# ZHSD-ZYNQ-PWR.net
KiCad netlist of a schematic drawn in Altium Designer
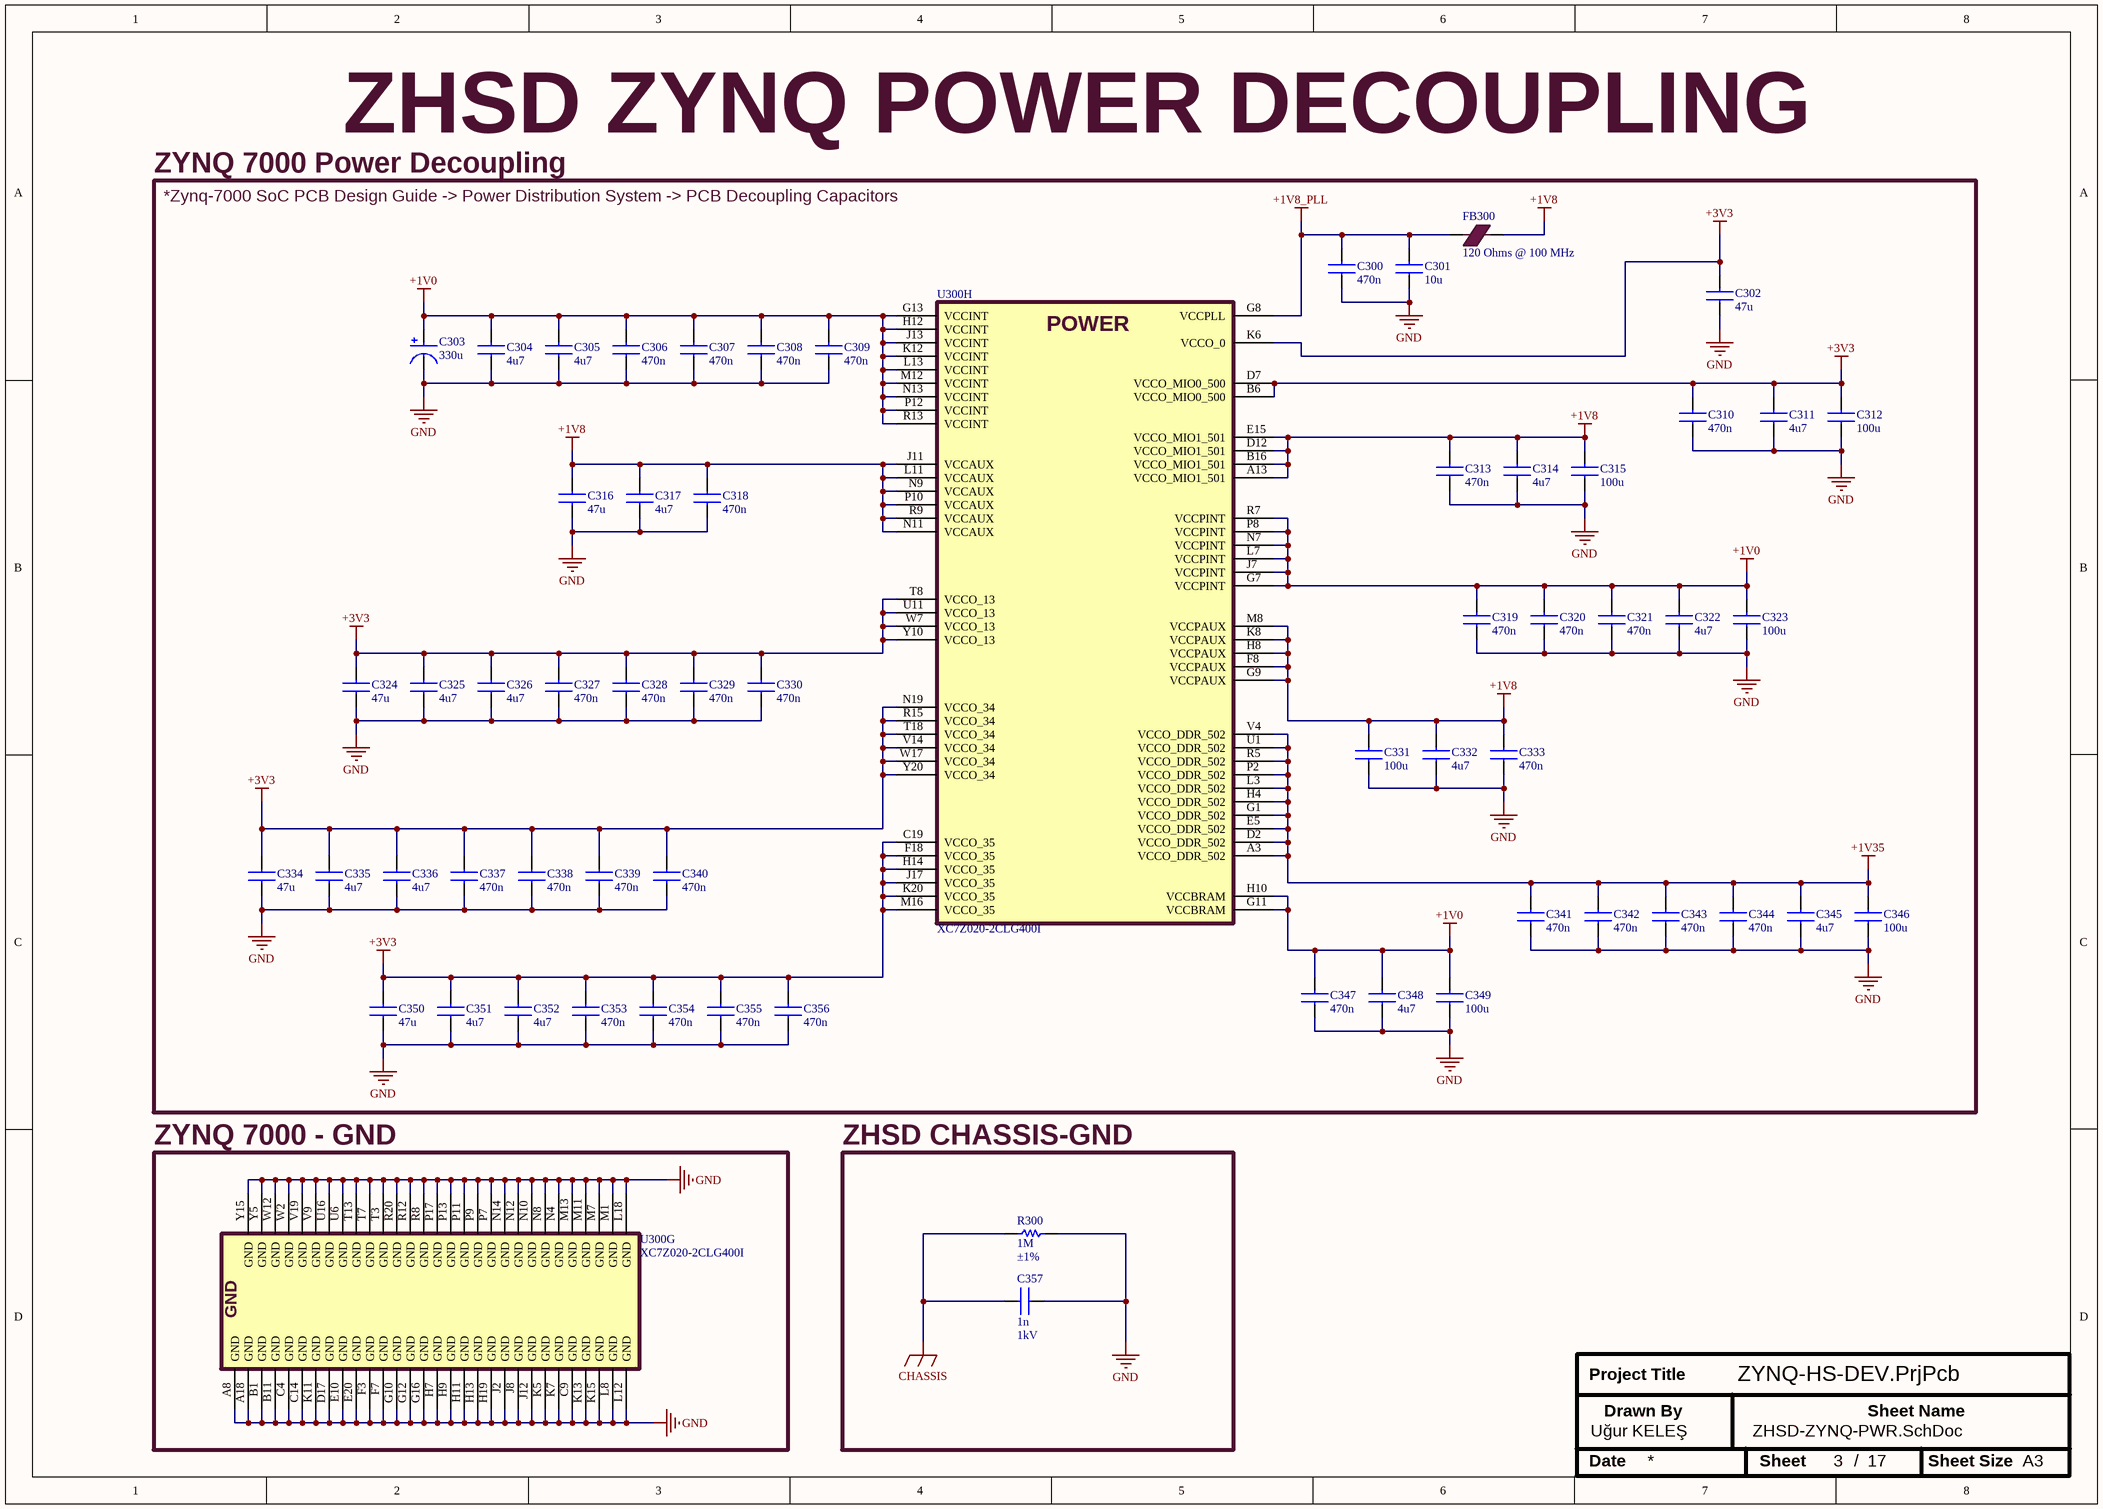
[diagram p0: ZHSD-ZYNQ-PWR.SchDoc]

(export (version "E")
  (design (tool "Eeschema 10.0.6"))
  (components
    (comp (ref "C300")
      (value "470n")
      (footprint "0402CAPC1005X06N")
      (description "CAP CER 0.47UF 6.3V X5R 0402(1005) ±10%")
      (fields (field (name "MANUFACTURER") "Murata Electronics") (field (name "MPN") "GRM155R60J474KE19D"))
      (libsource (lib "UK_Library") (part "GRM155R60J474KE19D"))
    )
    (comp (ref "C301")
      (value "10u")
      (footprint "0603CAPC1608X09N")
      (description "CAP CER 10UF 4V X5R 0603 (1608) ±20%")
      (fields (field (name "MANUFACTURER") "Murata Electronics") (field (name "MPN") "GRM188R60G106ME47D"))
      (libsource (lib "UK_Library") (part "GRM188R60G106ME47D"))
    )
    (comp (ref "C302")
      (value "47u")
      (footprint "1210CAPC3225X27N")
      (description "CAP CER 47UF 6.3V X7R 1210 1210 (3225) ±20%")
      (fields (field (name "MANUFACTURER") "Murata Electronics") (field (name "MPN") "GRM32ER70J476ME20L"))
      (libsource (lib "UK_Library") (part "GRM32ER70J476ME20L"))
    )
    (comp (ref "C303")
      (value "330u")
      (footprint "T525D337M006ATE025")
      (description "CAP TANT POLY 330UF 6.3V 2917 (7343) ±20%")
      (fields (field (name "MANUFACTURER") "KEMET") (field (name "MPN") "T525D337M006ATE025"))
      (libsource (lib "UK_Library") (part "T525D337M006ATE025"))
    )
    (comp (ref "C304")
      (value "4u7")
      (footprint "0603CAPC1608X09N")
      (description "CAP CER 4.7UF 10V X5R 0603 (1608) ±10%")
      (fields
        (field (name "MANUFACTURER") "Samsung Electro-Mechanics")
        (field (name "MPN") "CL10A475KP8NNNC")
      )
      (libsource (lib "UK_Library") (part "CL10A475KP8NNNC"))
    )
    (comp (ref "C305")
      (value "4u7")
      (footprint "0603CAPC1608X09N")
      (description "CAP CER 4.7UF 10V X5R 0603 (1608) ±10%")
      (fields
        (field (name "MANUFACTURER") "Samsung Electro-Mechanics")
        (field (name "MPN") "CL10A475KP8NNNC")
      )
      (libsource (lib "UK_Library") (part "CL10A475KP8NNNC"))
    )
    (comp (ref "C306")
      (value "470n")
      (footprint "0402CAPC1005X06N")
      (description "CAP CER 0.47UF 6.3V X5R 0402(1005) ±10%")
      (fields (field (name "MANUFACTURER") "Murata Electronics") (field (name "MPN") "GRM155R60J474KE19D"))
      (libsource (lib "UK_Library") (part "GRM155R60J474KE19D"))
    )
    (comp (ref "C307")
      (value "470n")
      (footprint "0402CAPC1005X06N")
      (description "CAP CER 0.47UF 6.3V X5R 0402(1005) ±10%")
      (fields (field (name "MANUFACTURER") "Murata Electronics") (field (name "MPN") "GRM155R60J474KE19D"))
      (libsource (lib "UK_Library") (part "GRM155R60J474KE19D"))
    )
    (comp (ref "C308")
      (value "470n")
      (footprint "0402CAPC1005X06N")
      (description "CAP CER 0.47UF 6.3V X5R 0402(1005) ±10%")
      (fields (field (name "MANUFACTURER") "Murata Electronics") (field (name "MPN") "GRM155R60J474KE19D"))
      (libsource (lib "UK_Library") (part "GRM155R60J474KE19D"))
    )
    (comp (ref "C309")
      (value "470n")
      (footprint "0402CAPC1005X06N")
      (description "CAP CER 0.47UF 6.3V X5R 0402(1005) ±10%")
      (fields (field (name "MANUFACTURER") "Murata Electronics") (field (name "MPN") "GRM155R60J474KE19D"))
      (libsource (lib "UK_Library") (part "GRM155R60J474KE19D"))
    )
    (comp (ref "C310")
      (value "470n")
      (footprint "0402CAPC1005X06N")
      (description "CAP CER 0.47UF 6.3V X5R 0402(1005) ±10%")
      (fields (field (name "MANUFACTURER") "Murata Electronics") (field (name "MPN") "GRM155R60J474KE19D"))
      (libsource (lib "UK_Library") (part "GRM155R60J474KE19D"))
    )
    (comp (ref "C311")
      (value "4u7")
      (footprint "0603CAPC1608X09N")
      (description "CAP CER 4.7UF 10V X5R 0603 (1608) ±10%")
      (fields
        (field (name "MANUFACTURER") "Samsung Electro-Mechanics")
        (field (name "MPN") "CL10A475KP8NNNC")
      )
      (libsource (lib "UK_Library") (part "CL10A475KP8NNNC"))
    )
    (comp (ref "C312")
      (value "100u")
      (footprint "1210CAPC3225X27N")
      (description "CAP CER 100UF 4V X7U 1210 (3225) ±20%")
      (fields (field (name "MANUFACTURER") "Murata Electronics") (field (name "MPN") "GRM32EE70G107ME19L"))
      (libsource (lib "UK_Library") (part "GRM32EE70G107ME19L"))
    )
    (comp (ref "C313")
      (value "470n")
      (footprint "0402CAPC1005X06N")
      (description "CAP CER 0.47UF 6.3V X5R 0402(1005) ±10%")
      (fields (field (name "MANUFACTURER") "Murata Electronics") (field (name "MPN") "GRM155R60J474KE19D"))
      (libsource (lib "UK_Library") (part "GRM155R60J474KE19D"))
    )
    (comp (ref "C314")
      (value "4u7")
      (footprint "0603CAPC1608X09N")
      (description "CAP CER 4.7UF 10V X5R 0603 (1608) ±10%")
      (fields
        (field (name "MANUFACTURER") "Samsung Electro-Mechanics")
        (field (name "MPN") "CL10A475KP8NNNC")
      )
      (libsource (lib "UK_Library") (part "CL10A475KP8NNNC"))
    )
    (comp (ref "C315")
      (value "100u")
      (footprint "1210CAPC3225X27N")
      (description "CAP CER 100UF 4V X7U 1210 (3225) ±20%")
      (fields (field (name "MANUFACTURER") "Murata Electronics") (field (name "MPN") "GRM32EE70G107ME19L"))
      (libsource (lib "UK_Library") (part "GRM32EE70G107ME19L"))
    )
    (comp (ref "C316")
      (value "47u")
      (footprint "1210CAPC3225X27N")
      (description "CAP CER 47UF 6.3V X7R 1210 1210 (3225) ±20%")
      (fields (field (name "MANUFACTURER") "Murata Electronics") (field (name "MPN") "GRM32ER70J476ME20L"))
      (libsource (lib "UK_Library") (part "GRM32ER70J476ME20L"))
    )
    (comp (ref "C317")
      (value "4u7")
      (footprint "0603CAPC1608X09N")
      (description "CAP CER 4.7UF 10V X5R 0603 (1608) ±10%")
      (fields
        (field (name "MANUFACTURER") "Samsung Electro-Mechanics")
        (field (name "MPN") "CL10A475KP8NNNC")
      )
      (libsource (lib "UK_Library") (part "CL10A475KP8NNNC"))
    )
    (comp (ref "C318")
      (value "470n")
      (footprint "0402CAPC1005X06N")
      (description "CAP CER 0.47UF 6.3V X5R 0402(1005) ±10%")
      (fields (field (name "MANUFACTURER") "Murata Electronics") (field (name "MPN") "GRM155R60J474KE19D"))
      (libsource (lib "UK_Library") (part "GRM155R60J474KE19D"))
    )
    (comp (ref "C319")
      (value "470n")
      (footprint "0402CAPC1005X06N")
      (description "CAP CER 0.47UF 6.3V X5R 0402(1005) ±10%")
      (fields (field (name "MANUFACTURER") "Murata Electronics") (field (name "MPN") "GRM155R60J474KE19D"))
      (libsource (lib "UK_Library") (part "GRM155R60J474KE19D"))
    )
    (comp (ref "C320")
      (value "470n")
      (footprint "0402CAPC1005X06N")
      (description "CAP CER 0.47UF 6.3V X5R 0402(1005) ±10%")
      (fields (field (name "MANUFACTURER") "Murata Electronics") (field (name "MPN") "GRM155R60J474KE19D"))
      (libsource (lib "UK_Library") (part "GRM155R60J474KE19D"))
    )
    (comp (ref "C321")
      (value "470n")
      (footprint "0402CAPC1005X06N")
      (description "CAP CER 0.47UF 6.3V X5R 0402(1005) ±10%")
      (fields (field (name "MANUFACTURER") "Murata Electronics") (field (name "MPN") "GRM155R60J474KE19D"))
      (libsource (lib "UK_Library") (part "GRM155R60J474KE19D"))
    )
    (comp (ref "C322")
      (value "4u7")
      (footprint "0603CAPC1608X09N")
      (description "CAP CER 4.7UF 10V X5R 0603 (1608) ±10%")
      (fields
        (field (name "MANUFACTURER") "Samsung Electro-Mechanics")
        (field (name "MPN") "CL10A475KP8NNNC")
      )
      (libsource (lib "UK_Library") (part "CL10A475KP8NNNC"))
    )
    (comp (ref "C323")
      (value "100u")
      (footprint "1210CAPC3225X27N")
      (description "CAP CER 100UF 4V X7U 1210 (3225) ±20%")
      (fields (field (name "MANUFACTURER") "Murata Electronics") (field (name "MPN") "GRM32EE70G107ME19L"))
      (libsource (lib "UK_Library") (part "GRM32EE70G107ME19L"))
    )
    (comp (ref "C324")
      (value "47u")
      (footprint "1210CAPC3225X27N")
      (description "CAP CER 47UF 6.3V X7R 1210 1210 (3225) ±20%")
      (fields (field (name "MANUFACTURER") "Murata Electronics") (field (name "MPN") "GRM32ER70J476ME20L"))
      (libsource (lib "UK_Library") (part "GRM32ER70J476ME20L"))
    )
    (comp (ref "C325")
      (value "4u7")
      (footprint "0603CAPC1608X09N")
      (description "CAP CER 4.7UF 10V X5R 0603 (1608) ±10%")
      (fields
        (field (name "MANUFACTURER") "Samsung Electro-Mechanics")
        (field (name "MPN") "CL10A475KP8NNNC")
      )
      (libsource (lib "UK_Library") (part "CL10A475KP8NNNC"))
    )
    (comp (ref "C326")
      (value "4u7")
      (footprint "0603CAPC1608X09N")
      (description "CAP CER 4.7UF 10V X5R 0603 (1608) ±10%")
      (fields
        (field (name "MANUFACTURER") "Samsung Electro-Mechanics")
        (field (name "MPN") "CL10A475KP8NNNC")
      )
      (libsource (lib "UK_Library") (part "CL10A475KP8NNNC"))
    )
    (comp (ref "C327")
      (value "470n")
      (footprint "0402CAPC1005X06N")
      (description "CAP CER 0.47UF 6.3V X5R 0402(1005) ±10%")
      (fields (field (name "MANUFACTURER") "Murata Electronics") (field (name "MPN") "GRM155R60J474KE19D"))
      (libsource (lib "UK_Library") (part "GRM155R60J474KE19D"))
    )
    (comp (ref "C328")
      (value "470n")
      (footprint "0402CAPC1005X06N")
      (description "CAP CER 0.47UF 6.3V X5R 0402(1005) ±10%")
      (fields (field (name "MANUFACTURER") "Murata Electronics") (field (name "MPN") "GRM155R60J474KE19D"))
      (libsource (lib "UK_Library") (part "GRM155R60J474KE19D"))
    )
    (comp (ref "C329")
      (value "470n")
      (footprint "0402CAPC1005X06N")
      (description "CAP CER 0.47UF 6.3V X5R 0402(1005) ±10%")
      (fields (field (name "MANUFACTURER") "Murata Electronics") (field (name "MPN") "GRM155R60J474KE19D"))
      (libsource (lib "UK_Library") (part "GRM155R60J474KE19D"))
    )
    (comp (ref "C330")
      (value "470n")
      (footprint "0402CAPC1005X06N")
      (description "CAP CER 0.47UF 6.3V X5R 0402(1005) ±10%")
      (fields (field (name "MANUFACTURER") "Murata Electronics") (field (name "MPN") "GRM155R60J474KE19D"))
      (libsource (lib "UK_Library") (part "GRM155R60J474KE19D"))
    )
    (comp (ref "C331")
      (value "100u")
      (footprint "1210CAPC3225X27N")
      (description "CAP CER 100UF 4V X7U 1210 (3225) ±20%")
      (fields (field (name "MANUFACTURER") "Murata Electronics") (field (name "MPN") "GRM32EE70G107ME19L"))
      (libsource (lib "UK_Library") (part "GRM32EE70G107ME19L"))
    )
    (comp (ref "C332")
      (value "4u7")
      (footprint "0603CAPC1608X09N")
      (description "CAP CER 4.7UF 10V X5R 0603 (1608) ±10%")
      (fields
        (field (name "MANUFACTURER") "Samsung Electro-Mechanics")
        (field (name "MPN") "CL10A475KP8NNNC")
      )
      (libsource (lib "UK_Library") (part "CL10A475KP8NNNC"))
    )
    (comp (ref "C333")
      (value "470n")
      (footprint "0402CAPC1005X06N")
      (description "CAP CER 0.47UF 6.3V X5R 0402(1005) ±10%")
      (fields (field (name "MANUFACTURER") "Murata Electronics") (field (name "MPN") "GRM155R60J474KE19D"))
      (libsource (lib "UK_Library") (part "GRM155R60J474KE19D"))
    )
    (comp (ref "C334")
      (value "47u")
      (footprint "1210CAPC3225X27N")
      (description "CAP CER 47UF 6.3V X7R 1210 1210 (3225) ±20%")
      (fields (field (name "MANUFACTURER") "Murata Electronics") (field (name "MPN") "GRM32ER70J476ME20L"))
      (libsource (lib "UK_Library") (part "GRM32ER70J476ME20L"))
    )
    (comp (ref "C335")
      (value "4u7")
      (footprint "0603CAPC1608X09N")
      (description "CAP CER 4.7UF 10V X5R 0603 (1608) ±10%")
      (fields
        (field (name "MANUFACTURER") "Samsung Electro-Mechanics")
        (field (name "MPN") "CL10A475KP8NNNC")
      )
      (libsource (lib "UK_Library") (part "CL10A475KP8NNNC"))
    )
    (comp (ref "C336")
      (value "4u7")
      (footprint "0603CAPC1608X09N")
      (description "CAP CER 4.7UF 10V X5R 0603 (1608) ±10%")
      (fields
        (field (name "MANUFACTURER") "Samsung Electro-Mechanics")
        (field (name "MPN") "CL10A475KP8NNNC")
      )
      (libsource (lib "UK_Library") (part "CL10A475KP8NNNC"))
    )
    (comp (ref "C337")
      (value "470n")
      (footprint "0402CAPC1005X06N")
      (description "CAP CER 0.47UF 6.3V X5R 0402(1005) ±10%")
      (fields (field (name "MANUFACTURER") "Murata Electronics") (field (name "MPN") "GRM155R60J474KE19D"))
      (libsource (lib "UK_Library") (part "GRM155R60J474KE19D"))
    )
    (comp (ref "C338")
      (value "470n")
      (footprint "0402CAPC1005X06N")
      (description "CAP CER 0.47UF 6.3V X5R 0402(1005) ±10%")
      (fields (field (name "MANUFACTURER") "Murata Electronics") (field (name "MPN") "GRM155R60J474KE19D"))
      (libsource (lib "UK_Library") (part "GRM155R60J474KE19D"))
    )
    (comp (ref "C339")
      (value "470n")
      (footprint "0402CAPC1005X06N")
      (description "CAP CER 0.47UF 6.3V X5R 0402(1005) ±10%")
      (fields (field (name "MANUFACTURER") "Murata Electronics") (field (name "MPN") "GRM155R60J474KE19D"))
      (libsource (lib "UK_Library") (part "GRM155R60J474KE19D"))
    )
    (comp (ref "C340")
      (value "470n")
      (footprint "0402CAPC1005X06N")
      (description "CAP CER 0.47UF 6.3V X5R 0402(1005) ±10%")
      (fields (field (name "MANUFACTURER") "Murata Electronics") (field (name "MPN") "GRM155R60J474KE19D"))
      (libsource (lib "UK_Library") (part "GRM155R60J474KE19D"))
    )
    (comp (ref "C341")
      (value "470n")
      (footprint "0402CAPC1005X06N")
      (description "CAP CER 0.47UF 6.3V X5R 0402(1005) ±10%")
      (fields (field (name "MANUFACTURER") "Murata Electronics") (field (name "MPN") "GRM155R60J474KE19D"))
      (libsource (lib "UK_Library") (part "GRM155R60J474KE19D"))
    )
    (comp (ref "C342")
      (value "470n")
      (footprint "0402CAPC1005X06N")
      (description "CAP CER 0.47UF 6.3V X5R 0402(1005) ±10%")
      (fields (field (name "MANUFACTURER") "Murata Electronics") (field (name "MPN") "GRM155R60J474KE19D"))
      (libsource (lib "UK_Library") (part "GRM155R60J474KE19D"))
    )
    (comp (ref "C343")
      (value "470n")
      (footprint "0402CAPC1005X06N")
      (description "CAP CER 0.47UF 6.3V X5R 0402(1005) ±10%")
      (fields (field (name "MANUFACTURER") "Murata Electronics") (field (name "MPN") "GRM155R60J474KE19D"))
      (libsource (lib "UK_Library") (part "GRM155R60J474KE19D"))
    )
    (comp (ref "C344")
      (value "470n")
      (footprint "0402CAPC1005X06N")
      (description "CAP CER 0.47UF 6.3V X5R 0402(1005) ±10%")
      (fields (field (name "MANUFACTURER") "Murata Electronics") (field (name "MPN") "GRM155R60J474KE19D"))
      (libsource (lib "UK_Library") (part "GRM155R60J474KE19D"))
    )
    (comp (ref "C345")
      (value "4u7")
      (footprint "0603CAPC1608X09N")
      (description "CAP CER 4.7UF 10V X5R 0603 (1608) ±10%")
      (fields
        (field (name "MANUFACTURER") "Samsung Electro-Mechanics")
        (field (name "MPN") "CL10A475KP8NNNC")
      )
      (libsource (lib "UK_Library") (part "CL10A475KP8NNNC"))
    )
    (comp (ref "C346")
      (value "100u")
      (footprint "1210CAPC3225X27N")
      (description "CAP CER 100UF 4V X7U 1210 (3225) ±20%")
      (fields (field (name "MANUFACTURER") "Murata Electronics") (field (name "MPN") "GRM32EE70G107ME19L"))
      (libsource (lib "UK_Library") (part "GRM32EE70G107ME19L"))
    )
    (comp (ref "C347")
      (value "470n")
      (footprint "0402CAPC1005X06N")
      (description "CAP CER 0.47UF 6.3V X5R 0402(1005) ±10%")
      (fields (field (name "MANUFACTURER") "Murata Electronics") (field (name "MPN") "GRM155R60J474KE19D"))
      (libsource (lib "UK_Library") (part "GRM155R60J474KE19D"))
    )
    (comp (ref "C348")
      (value "4u7")
      (footprint "0603CAPC1608X09N")
      (description "CAP CER 4.7UF 10V X5R 0603 (1608) ±10%")
      (fields
        (field (name "MANUFACTURER") "Samsung Electro-Mechanics")
        (field (name "MPN") "CL10A475KP8NNNC")
      )
      (libsource (lib "UK_Library") (part "CL10A475KP8NNNC"))
    )
    (comp (ref "C349")
      (value "100u")
      (footprint "1210CAPC3225X27N")
      (description "CAP CER 100UF 4V X7U 1210 (3225) ±20%")
      (fields (field (name "MANUFACTURER") "Murata Electronics") (field (name "MPN") "GRM32EE70G107ME19L"))
      (libsource (lib "UK_Library") (part "GRM32EE70G107ME19L"))
    )
    (comp (ref "C350")
      (value "47u")
      (footprint "1210CAPC3225X27N")
      (description "CAP CER 47UF 6.3V X7R 1210 1210 (3225) ±20%")
      (fields (field (name "MANUFACTURER") "Murata Electronics") (field (name "MPN") "GRM32ER70J476ME20L"))
      (libsource (lib "UK_Library") (part "GRM32ER70J476ME20L"))
    )
    (comp (ref "C351")
      (value "4u7")
      (footprint "0603CAPC1608X09N")
      (description "CAP CER 4.7UF 10V X5R 0603 (1608) ±10%")
      (fields
        (field (name "MANUFACTURER") "Samsung Electro-Mechanics")
        (field (name "MPN") "CL10A475KP8NNNC")
      )
      (libsource (lib "UK_Library") (part "CL10A475KP8NNNC"))
    )
    (comp (ref "C352")
      (value "4u7")
      (footprint "0603CAPC1608X09N")
      (description "CAP CER 4.7UF 10V X5R 0603 (1608) ±10%")
      (fields
        (field (name "MANUFACTURER") "Samsung Electro-Mechanics")
        (field (name "MPN") "CL10A475KP8NNNC")
      )
      (libsource (lib "UK_Library") (part "CL10A475KP8NNNC"))
    )
    (comp (ref "C353")
      (value "470n")
      (footprint "0402CAPC1005X06N")
      (description "CAP CER 0.47UF 6.3V X5R 0402(1005) ±10%")
      (fields (field (name "MANUFACTURER") "Murata Electronics") (field (name "MPN") "GRM155R60J474KE19D"))
      (libsource (lib "UK_Library") (part "GRM155R60J474KE19D"))
    )
    (comp (ref "C354")
      (value "470n")
      (footprint "0402CAPC1005X06N")
      (description "CAP CER 0.47UF 6.3V X5R 0402(1005) ±10%")
      (fields (field (name "MANUFACTURER") "Murata Electronics") (field (name "MPN") "GRM155R60J474KE19D"))
      (libsource (lib "UK_Library") (part "GRM155R60J474KE19D"))
    )
    (comp (ref "C355")
      (value "470n")
      (footprint "0402CAPC1005X06N")
      (description "CAP CER 0.47UF 6.3V X5R 0402(1005) ±10%")
      (fields (field (name "MANUFACTURER") "Murata Electronics") (field (name "MPN") "GRM155R60J474KE19D"))
      (libsource (lib "UK_Library") (part "GRM155R60J474KE19D"))
    )
    (comp (ref "C356")
      (value "470n")
      (footprint "0402CAPC1005X06N")
      (description "CAP CER 0.47UF 6.3V X5R 0402(1005) ±10%")
      (fields (field (name "MANUFACTURER") "Murata Electronics") (field (name "MPN") "GRM155R60J474KE19D"))
      (libsource (lib "UK_Library") (part "GRM155R60J474KE19D"))
    )
    (comp (ref "C357")
      (value "1n")
      (footprint "0805CAPC2012X14N")
      (description "CAP CER 1000PF 1KV X7R 0805 (2012) ±10%")
      (fields
        (field (name "MANUFACTURER") "YAGEO")
        (field (name "MPN") "CC0805KRX7RCBB102")
        (field (name "VOLTAGE") "1kV")
      )
      (libsource (lib "UK_Library") (part "CC0805KRX7RCBB102"))
    )
    (comp (ref "FB300")
      (value "120 Ohms @ 100 MHz")
      (footprint "0603INDC1608X08N")
      (description "FERRITE BEAD 120 OHM 0603 (1608) 3A 25mOhm")
      (fields (field (name "MANUFACTURER") "Murata Electronics") (field (name "MPN") "BLM18SG121TN1D"))
      (libsource (lib "UK_Library") (part "BLM18SG121TN1D"))
    )
    (comp (ref "R300")
      (value "1M")
      (footprint "0603RESC1608X05N")
      (description "RES SMD 1M OHM 1% 1/8W 0603 (1608)")
      (fields
        (field (name "MANUFACTURER") "Vishay Dale")
        (field (name "MPN") "CRCW06031M00FKEA")
        (field (name "TOLERANCE") "±1%")
      )
      (libsource (lib "UK_Library") (part "CRCW06031M00FKEA"))
    )
    (comp (ref "U300")
      (value "XC7Z020-2CLG400I")
      (footprint "BGA400C80P20X20_1700X1700X147")
      (fields (field (name "MANUFACTURER") "AMD/XILINX"))
      (libsource (lib "UK_Library") (part "XC7Z020-2CLG400I"))
    )
  )
  (nets
    (net (code "1") (name "+1V0") (class "Default")
      (node (ref "C303") (pin "1") (pinfunction "1_1") (pintype "passive"))
      (node (ref "C304") (pin "2") (pinfunction "2_2") (pintype "passive"))
      (node (ref "C305") (pin "2") (pinfunction "2_2") (pintype "passive"))
      (node (ref "C306") (pin "2") (pinfunction "2_2") (pintype "passive"))
      (node (ref "C307") (pin "2") (pinfunction "2_2") (pintype "passive"))
      (node (ref "C308") (pin "2") (pinfunction "2_2") (pintype "passive"))
      (node (ref "C309") (pin "2") (pinfunction "2_2") (pintype "passive"))
      (node (ref "C319") (pin "2") (pinfunction "2_2") (pintype "passive"))
      (node (ref "C320") (pin "2") (pinfunction "2_2") (pintype "passive"))
      (node (ref "C321") (pin "2") (pinfunction "2_2") (pintype "passive"))
      (node (ref "C322") (pin "2") (pinfunction "2_2") (pintype "passive"))
      (node (ref "C323") (pin "1") (pinfunction "1_1") (pintype "passive"))
      (node (ref "C347") (pin "2") (pinfunction "2_2") (pintype "passive"))
      (node (ref "C348") (pin "2") (pinfunction "2_2") (pintype "passive"))
      (node (ref "C349") (pin "1") (pinfunction "1_1") (pintype "passive"))
      (node (ref "U300") (pin "G11") (pinfunction "VCCBRAM_G11") (pintype "power_in"))
      (node (ref "U300") (pin "G13") (pinfunction "VCCINT_G13") (pintype "power_in"))
      (node (ref "U300") (pin "G7") (pinfunction "VCCPINT_G7") (pintype "power_in"))
      (node (ref "U300") (pin "H10") (pinfunction "VCCBRAM_H10") (pintype "power_in"))
      (node (ref "U300") (pin "H12") (pinfunction "VCCINT_H12") (pintype "power_in"))
      (node (ref "U300") (pin "J13") (pinfunction "VCCINT_J13") (pintype "power_in"))
      (node (ref "U300") (pin "J7") (pinfunction "VCCPINT_J7") (pintype "power_in"))
      (node (ref "U300") (pin "K12") (pinfunction "VCCINT_K12") (pintype "power_in"))
      (node (ref "U300") (pin "L13") (pinfunction "VCCINT_L13") (pintype "power_in"))
      (node (ref "U300") (pin "L7") (pinfunction "VCCPINT_L7") (pintype "power_in"))
      (node (ref "U300") (pin "M12") (pinfunction "VCCINT_M12") (pintype "power_in"))
      (node (ref "U300") (pin "N13") (pinfunction "VCCINT_N13") (pintype "power_in"))
      (node (ref "U300") (pin "N7") (pinfunction "VCCPINT_N7") (pintype "power_in"))
      (node (ref "U300") (pin "P12") (pinfunction "VCCINT_P12") (pintype "power_in"))
      (node (ref "U300") (pin "P8") (pinfunction "VCCPINT_P8") (pintype "power_in"))
      (node (ref "U300") (pin "R13") (pinfunction "VCCINT_R13") (pintype "power_in"))
      (node (ref "U300") (pin "R7") (pinfunction "VCCPINT_R7") (pintype "power_in"))
    )
    (net (code "2") (name "+1V8") (class "Default")
      (node (ref "C313") (pin "2") (pinfunction "2_2") (pintype "passive"))
      (node (ref "C314") (pin "2") (pinfunction "2_2") (pintype "passive"))
      (node (ref "C315") (pin "1") (pinfunction "1_1") (pintype "passive"))
      (node (ref "C316") (pin "2") (pinfunction "2_2") (pintype "passive"))
      (node (ref "C317") (pin "2") (pinfunction "2_2") (pintype "passive"))
      (node (ref "C318") (pin "2") (pinfunction "2_2") (pintype "passive"))
      (node (ref "C331") (pin "1") (pinfunction "1_1") (pintype "passive"))
      (node (ref "C332") (pin "2") (pinfunction "2_2") (pintype "passive"))
      (node (ref "C333") (pin "2") (pinfunction "2_2") (pintype "passive"))
      (node (ref "FB300") (pin "2") (pinfunction "2_2") (pintype "passive"))
      (node (ref "U300") (pin "A13") (pinfunction "VCCO_MIO1_501_A13") (pintype "power_in"))
      (node (ref "U300") (pin "B16") (pinfunction "VCCO_MIO1_501_B16") (pintype "power_in"))
      (node (ref "U300") (pin "D12") (pinfunction "VCCO_MIO1_501_D12") (pintype "power_in"))
      (node (ref "U300") (pin "E15") (pinfunction "VCCO_MIO1_501_E15") (pintype "power_in"))
      (node (ref "U300") (pin "F8") (pinfunction "VCCPAUX_F8") (pintype "power_in"))
      (node (ref "U300") (pin "G9") (pinfunction "VCCPAUX_G9") (pintype "power_in"))
      (node (ref "U300") (pin "H8") (pinfunction "VCCPAUX_H8") (pintype "power_in"))
      (node (ref "U300") (pin "J11") (pinfunction "VCCAUX_J11") (pintype "power_in"))
      (node (ref "U300") (pin "K8") (pinfunction "VCCPAUX_K8") (pintype "power_in"))
      (node (ref "U300") (pin "L11") (pinfunction "VCCAUX_L11") (pintype "power_in"))
      (node (ref "U300") (pin "M8") (pinfunction "VCCPAUX_M8") (pintype "power_in"))
      (node (ref "U300") (pin "N11") (pinfunction "VCCAUX_N11") (pintype "power_in"))
      (node (ref "U300") (pin "N9") (pinfunction "VCCAUX_N9") (pintype "power_in"))
      (node (ref "U300") (pin "P10") (pinfunction "VCCAUX_P10") (pintype "power_in"))
      (node (ref "U300") (pin "R9") (pinfunction "VCCAUX_R9") (pintype "power_in"))
    )
    (net (code "3") (name "+1V8_PLL") (class "Default")
      (node (ref "C300") (pin "2") (pinfunction "2_2") (pintype "passive"))
      (node (ref "C301") (pin "2") (pinfunction "2_2") (pintype "passive"))
      (node (ref "FB300") (pin "1") (pinfunction "1_1") (pintype "passive"))
      (node (ref "U300") (pin "G8") (pinfunction "VCCPLL_G8") (pintype "power_in"))
    )
    (net (code "4") (name "+1V35") (class "Default")
      (node (ref "C341") (pin "2") (pinfunction "2_2") (pintype "passive"))
      (node (ref "C342") (pin "2") (pinfunction "2_2") (pintype "passive"))
      (node (ref "C343") (pin "2") (pinfunction "2_2") (pintype "passive"))
      (node (ref "C344") (pin "2") (pinfunction "2_2") (pintype "passive"))
      (node (ref "C345") (pin "2") (pinfunction "2_2") (pintype "passive"))
      (node (ref "C346") (pin "1") (pinfunction "1_1") (pintype "passive"))
      (node (ref "U300") (pin "A3") (pinfunction "VCCO_DDR_502_A3") (pintype "power_in"))
      (node (ref "U300") (pin "D2") (pinfunction "VCCO_DDR_502_D2") (pintype "power_in"))
      (node (ref "U300") (pin "E5") (pinfunction "VCCO_DDR_502_E5") (pintype "power_in"))
      (node (ref "U300") (pin "G1") (pinfunction "VCCO_DDR_502_G1") (pintype "power_in"))
      (node (ref "U300") (pin "H4") (pinfunction "VCCO_DDR_502_H4") (pintype "power_in"))
      (node (ref "U300") (pin "L3") (pinfunction "VCCO_DDR_502_L3") (pintype "power_in"))
      (node (ref "U300") (pin "P2") (pinfunction "VCCO_DDR_502_P2") (pintype "power_in"))
      (node (ref "U300") (pin "R5") (pinfunction "VCCO_DDR_502_R5") (pintype "power_in"))
      (node (ref "U300") (pin "U1") (pinfunction "VCCO_DDR_502_U1") (pintype "power_in"))
      (node (ref "U300") (pin "V4") (pinfunction "VCCO_DDR_502_V4") (pintype "power_in"))
    )
    (net (code "5") (name "+3V3") (class "Default")
      (node (ref "C302") (pin "2") (pinfunction "2_2") (pintype "passive"))
      (node (ref "C310") (pin "2") (pinfunction "2_2") (pintype "passive"))
      (node (ref "C311") (pin "2") (pinfunction "2_2") (pintype "passive"))
      (node (ref "C312") (pin "1") (pinfunction "1_1") (pintype "passive"))
      (node (ref "C324") (pin "2") (pinfunction "2_2") (pintype "passive"))
      (node (ref "C325") (pin "2") (pinfunction "2_2") (pintype "passive"))
      (node (ref "C326") (pin "2") (pinfunction "2_2") (pintype "passive"))
      (node (ref "C327") (pin "2") (pinfunction "2_2") (pintype "passive"))
      (node (ref "C328") (pin "2") (pinfunction "2_2") (pintype "passive"))
      (node (ref "C329") (pin "2") (pinfunction "2_2") (pintype "passive"))
      (node (ref "C330") (pin "2") (pinfunction "2_2") (pintype "passive"))
      (node (ref "C334") (pin "2") (pinfunction "2_2") (pintype "passive"))
      (node (ref "C335") (pin "2") (pinfunction "2_2") (pintype "passive"))
      (node (ref "C336") (pin "2") (pinfunction "2_2") (pintype "passive"))
      (node (ref "C337") (pin "2") (pinfunction "2_2") (pintype "passive"))
      (node (ref "C338") (pin "2") (pinfunction "2_2") (pintype "passive"))
      (node (ref "C339") (pin "2") (pinfunction "2_2") (pintype "passive"))
      (node (ref "C340") (pin "2") (pinfunction "2_2") (pintype "passive"))
      (node (ref "C350") (pin "2") (pinfunction "2_2") (pintype "passive"))
      (node (ref "C351") (pin "2") (pinfunction "2_2") (pintype "passive"))
      (node (ref "C352") (pin "2") (pinfunction "2_2") (pintype "passive"))
      (node (ref "C353") (pin "2") (pinfunction "2_2") (pintype "passive"))
      (node (ref "C354") (pin "2") (pinfunction "2_2") (pintype "passive"))
      (node (ref "C355") (pin "2") (pinfunction "2_2") (pintype "passive"))
      (node (ref "C356") (pin "2") (pinfunction "2_2") (pintype "passive"))
      (node (ref "U300") (pin "B6") (pinfunction "VCCO_MIO0_500_B6") (pintype "power_in"))
      (node (ref "U300") (pin "C19") (pinfunction "VCCO_35_C19") (pintype "power_in"))
      (node (ref "U300") (pin "D7") (pinfunction "VCCO_MIO0_500_D7") (pintype "power_in"))
      (node (ref "U300") (pin "F18") (pinfunction "VCCO_35_F18") (pintype "power_in"))
      (node (ref "U300") (pin "H14") (pinfunction "VCCO_35_H14") (pintype "power_in"))
      (node (ref "U300") (pin "J17") (pinfunction "VCCO_35_J17") (pintype "power_in"))
      (node (ref "U300") (pin "K20") (pinfunction "VCCO_35_K20") (pintype "power_in"))
      (node (ref "U300") (pin "K6") (pinfunction "VCCO_0_K6") (pintype "power_in"))
      (node (ref "U300") (pin "M16") (pinfunction "VCCO_35_M16") (pintype "power_in"))
      (node (ref "U300") (pin "N19") (pinfunction "VCCO_34_N19") (pintype "power_in"))
      (node (ref "U300") (pin "R15") (pinfunction "VCCO_34_R15") (pintype "power_in"))
      (node (ref "U300") (pin "T18") (pinfunction "VCCO_34_T18") (pintype "power_in"))
      (node (ref "U300") (pin "T8") (pinfunction "VCCO_13_T8") (pintype "power_in"))
      (node (ref "U300") (pin "U11") (pinfunction "VCCO_13_U11") (pintype "power_in"))
      (node (ref "U300") (pin "V14") (pinfunction "VCCO_34_V14") (pintype "power_in"))
      (node (ref "U300") (pin "W17") (pinfunction "VCCO_34_W17") (pintype "power_in"))
      (node (ref "U300") (pin "W7") (pinfunction "VCCO_13_W7") (pintype "power_in"))
      (node (ref "U300") (pin "Y10") (pinfunction "VCCO_13_Y10") (pintype "power_in"))
      (node (ref "U300") (pin "Y20") (pinfunction "VCCO_34_Y20") (pintype "power_in"))
    )
    (net (code "6") (name "CHASSIS") (class "Default")
      (node (ref "C357") (pin "2") (pinfunction "2_2") (pintype "passive"))
      (node (ref "R300") (pin "1") (pinfunction "1_1") (pintype "passive"))
    )
    (net (code "7") (name "GND") (class "Default")
      (node (ref "C300") (pin "1") (pinfunction "1_1") (pintype "passive"))
      (node (ref "C301") (pin "1") (pinfunction "1_1") (pintype "passive"))
      (node (ref "C302") (pin "1") (pinfunction "1_1") (pintype "passive"))
      (node (ref "C303") (pin "2") (pinfunction "2_2") (pintype "passive"))
      (node (ref "C304") (pin "1") (pinfunction "1_1") (pintype "passive"))
      (node (ref "C305") (pin "1") (pinfunction "1_1") (pintype "passive"))
      (node (ref "C306") (pin "1") (pinfunction "1_1") (pintype "passive"))
      (node (ref "C307") (pin "1") (pinfunction "1_1") (pintype "passive"))
      (node (ref "C308") (pin "1") (pinfunction "1_1") (pintype "passive"))
      (node (ref "C309") (pin "1") (pinfunction "1_1") (pintype "passive"))
      (node (ref "C310") (pin "1") (pinfunction "1_1") (pintype "passive"))
      (node (ref "C311") (pin "1") (pinfunction "1_1") (pintype "passive"))
      (node (ref "C312") (pin "2") (pinfunction "2_2") (pintype "passive"))
      (node (ref "C313") (pin "1") (pinfunction "1_1") (pintype "passive"))
      (node (ref "C314") (pin "1") (pinfunction "1_1") (pintype "passive"))
      (node (ref "C315") (pin "2") (pinfunction "2_2") (pintype "passive"))
      (node (ref "C316") (pin "1") (pinfunction "1_1") (pintype "passive"))
      (node (ref "C317") (pin "1") (pinfunction "1_1") (pintype "passive"))
      (node (ref "C318") (pin "1") (pinfunction "1_1") (pintype "passive"))
      (node (ref "C319") (pin "1") (pinfunction "1_1") (pintype "passive"))
      (node (ref "C320") (pin "1") (pinfunction "1_1") (pintype "passive"))
      (node (ref "C321") (pin "1") (pinfunction "1_1") (pintype "passive"))
      (node (ref "C322") (pin "1") (pinfunction "1_1") (pintype "passive"))
      (node (ref "C323") (pin "2") (pinfunction "2_2") (pintype "passive"))
      (node (ref "C324") (pin "1") (pinfunction "1_1") (pintype "passive"))
      (node (ref "C325") (pin "1") (pinfunction "1_1") (pintype "passive"))
      (node (ref "C326") (pin "1") (pinfunction "1_1") (pintype "passive"))
      (node (ref "C327") (pin "1") (pinfunction "1_1") (pintype "passive"))
      (node (ref "C328") (pin "1") (pinfunction "1_1") (pintype "passive"))
      (node (ref "C329") (pin "1") (pinfunction "1_1") (pintype "passive"))
      (node (ref "C330") (pin "1") (pinfunction "1_1") (pintype "passive"))
      (node (ref "C331") (pin "2") (pinfunction "2_2") (pintype "passive"))
      (node (ref "C332") (pin "1") (pinfunction "1_1") (pintype "passive"))
      (node (ref "C333") (pin "1") (pinfunction "1_1") (pintype "passive"))
      (node (ref "C334") (pin "1") (pinfunction "1_1") (pintype "passive"))
      (node (ref "C335") (pin "1") (pinfunction "1_1") (pintype "passive"))
      (node (ref "C336") (pin "1") (pinfunction "1_1") (pintype "passive"))
      (node (ref "C337") (pin "1") (pinfunction "1_1") (pintype "passive"))
      (node (ref "C338") (pin "1") (pinfunction "1_1") (pintype "passive"))
      (node (ref "C339") (pin "1") (pinfunction "1_1") (pintype "passive"))
      (node (ref "C340") (pin "1") (pinfunction "1_1") (pintype "passive"))
      (node (ref "C341") (pin "1") (pinfunction "1_1") (pintype "passive"))
      (node (ref "C342") (pin "1") (pinfunction "1_1") (pintype "passive"))
      (node (ref "C343") (pin "1") (pinfunction "1_1") (pintype "passive"))
      (node (ref "C344") (pin "1") (pinfunction "1_1") (pintype "passive"))
      (node (ref "C345") (pin "1") (pinfunction "1_1") (pintype "passive"))
      (node (ref "C346") (pin "2") (pinfunction "2_2") (pintype "passive"))
      (node (ref "C347") (pin "1") (pinfunction "1_1") (pintype "passive"))
      (node (ref "C348") (pin "1") (pinfunction "1_1") (pintype "passive"))
      (node (ref "C349") (pin "2") (pinfunction "2_2") (pintype "passive"))
      (node (ref "C350") (pin "1") (pinfunction "1_1") (pintype "passive"))
      (node (ref "C351") (pin "1") (pinfunction "1_1") (pintype "passive"))
      (node (ref "C352") (pin "1") (pinfunction "1_1") (pintype "passive"))
      (node (ref "C353") (pin "1") (pinfunction "1_1") (pintype "passive"))
      (node (ref "C354") (pin "1") (pinfunction "1_1") (pintype "passive"))
      (node (ref "C355") (pin "1") (pinfunction "1_1") (pintype "passive"))
      (node (ref "C356") (pin "1") (pinfunction "1_1") (pintype "passive"))
      (node (ref "C357") (pin "1") (pinfunction "1_1") (pintype "passive"))
      (node (ref "R300") (pin "2") (pinfunction "2_2") (pintype "passive"))
      (node (ref "U300") (pin "A18") (pinfunction "GND_A18") (pintype "power_in"))
      (node (ref "U300") (pin "A8") (pinfunction "GND_A8") (pintype "power_in"))
      (node (ref "U300") (pin "B1") (pinfunction "GND_B1") (pintype "power_in"))
      (node (ref "U300") (pin "B11") (pinfunction "GND_B11") (pintype "power_in"))
      (node (ref "U300") (pin "C14") (pinfunction "GND_C14") (pintype "power_in"))
      (node (ref "U300") (pin "C4") (pinfunction "GND_C4") (pintype "power_in"))
      (node (ref "U300") (pin "C9") (pinfunction "GND_C9") (pintype "power_in"))
      (node (ref "U300") (pin "D17") (pinfunction "GND_D17") (pintype "power_in"))
      (node (ref "U300") (pin "E10") (pinfunction "GND_E10") (pintype "power_in"))
      (node (ref "U300") (pin "E20") (pinfunction "GND_E20") (pintype "power_in"))
      (node (ref "U300") (pin "F3") (pinfunction "GND_F3") (pintype "power_in"))
      (node (ref "U300") (pin "F7") (pinfunction "GND_F7") (pintype "power_in"))
      (node (ref "U300") (pin "G10") (pinfunction "GND_G10") (pintype "power_in"))
      (node (ref "U300") (pin "G12") (pinfunction "GND_G12") (pintype "power_in"))
      (node (ref "U300") (pin "G16") (pinfunction "GND_G16") (pintype "power_in"))
      (node (ref "U300") (pin "H11") (pinfunction "GND_H11") (pintype "power_in"))
      (node (ref "U300") (pin "H13") (pinfunction "GND_H13") (pintype "power_in"))
      (node (ref "U300") (pin "H19") (pinfunction "GND_H19") (pintype "power_in"))
      (node (ref "U300") (pin "H7") (pinfunction "GND_H7") (pintype "power_in"))
      (node (ref "U300") (pin "H9") (pinfunction "GND_H9") (pintype "power_in"))
      (node (ref "U300") (pin "J12") (pinfunction "GND_J12") (pintype "power_in"))
      (node (ref "U300") (pin "J2") (pinfunction "GND_J2") (pintype "power_in"))
      (node (ref "U300") (pin "J8") (pinfunction "GND_J8") (pintype "power_in"))
      (node (ref "U300") (pin "K11") (pinfunction "GND_K11") (pintype "power_in"))
      (node (ref "U300") (pin "K13") (pinfunction "GND_K13") (pintype "power_in"))
      (node (ref "U300") (pin "K15") (pinfunction "GND_K15") (pintype "power_in"))
      (node (ref "U300") (pin "K5") (pinfunction "GND_K5") (pintype "power_in"))
      (node (ref "U300") (pin "K7") (pinfunction "GND_K7") (pintype "power_in"))
      (node (ref "U300") (pin "L12") (pinfunction "GND_L12") (pintype "power_in"))
      (node (ref "U300") (pin "L18") (pinfunction "GND_L18") (pintype "power_in"))
      (node (ref "U300") (pin "L8") (pinfunction "GND_L8") (pintype "power_in"))
      (node (ref "U300") (pin "M1") (pinfunction "GND_M1") (pintype "power_in"))
      (node (ref "U300") (pin "M11") (pinfunction "GND_M11") (pintype "power_in"))
      (node (ref "U300") (pin "M13") (pinfunction "GND_M13") (pintype "power_in"))
      (node (ref "U300") (pin "M7") (pinfunction "GND_M7") (pintype "power_in"))
      (node (ref "U300") (pin "N10") (pinfunction "GND_N10") (pintype "power_in"))
      (node (ref "U300") (pin "N12") (pinfunction "GND_N12") (pintype "power_in"))
      (node (ref "U300") (pin "N14") (pinfunction "GND_N14") (pintype "power_in"))
      (node (ref "U300") (pin "N4") (pinfunction "GND_N4") (pintype "power_in"))
      (node (ref "U300") (pin "N8") (pinfunction "GND_N8") (pintype "power_in"))
      (node (ref "U300") (pin "P11") (pinfunction "GND_P11") (pintype "power_in"))
      (node (ref "U300") (pin "P13") (pinfunction "GND_P13") (pintype "power_in"))
      (node (ref "U300") (pin "P17") (pinfunction "GND_P17") (pintype "power_in"))
      (node (ref "U300") (pin "P7") (pinfunction "GND_P7") (pintype "power_in"))
      (node (ref "U300") (pin "P9") (pinfunction "GND_P9") (pintype "power_in"))
      (node (ref "U300") (pin "R12") (pinfunction "GND_R12") (pintype "power_in"))
      (node (ref "U300") (pin "R20") (pinfunction "GND_R20") (pintype "power_in"))
      (node (ref "U300") (pin "R8") (pinfunction "GND_R8") (pintype "power_in"))
      (node (ref "U300") (pin "T13") (pinfunction "GND_T13") (pintype "power_in"))
      (node (ref "U300") (pin "T3") (pinfunction "GND_T3") (pintype "power_in"))
      (node (ref "U300") (pin "T7") (pinfunction "GND_T7") (pintype "power_in"))
      (node (ref "U300") (pin "U16") (pinfunction "GND_U16") (pintype "power_in"))
      (node (ref "U300") (pin "U6") (pinfunction "GND_U6") (pintype "power_in"))
      (node (ref "U300") (pin "V19") (pinfunction "GND_V19") (pintype "power_in"))
      (node (ref "U300") (pin "V9") (pinfunction "GND_V9") (pintype "power_in"))
      (node (ref "U300") (pin "W12") (pinfunction "GND_W12") (pintype "power_in"))
      (node (ref "U300") (pin "W2") (pinfunction "GND_W2") (pintype "power_in"))
      (node (ref "U300") (pin "Y15") (pinfunction "GND_Y15") (pintype "power_in"))
      (node (ref "U300") (pin "Y5") (pinfunction "GND_Y5") (pintype "power_in"))
    )
  )
)
